# GLCD.net
KiCad netlist of a schematic drawn in Altium Designer
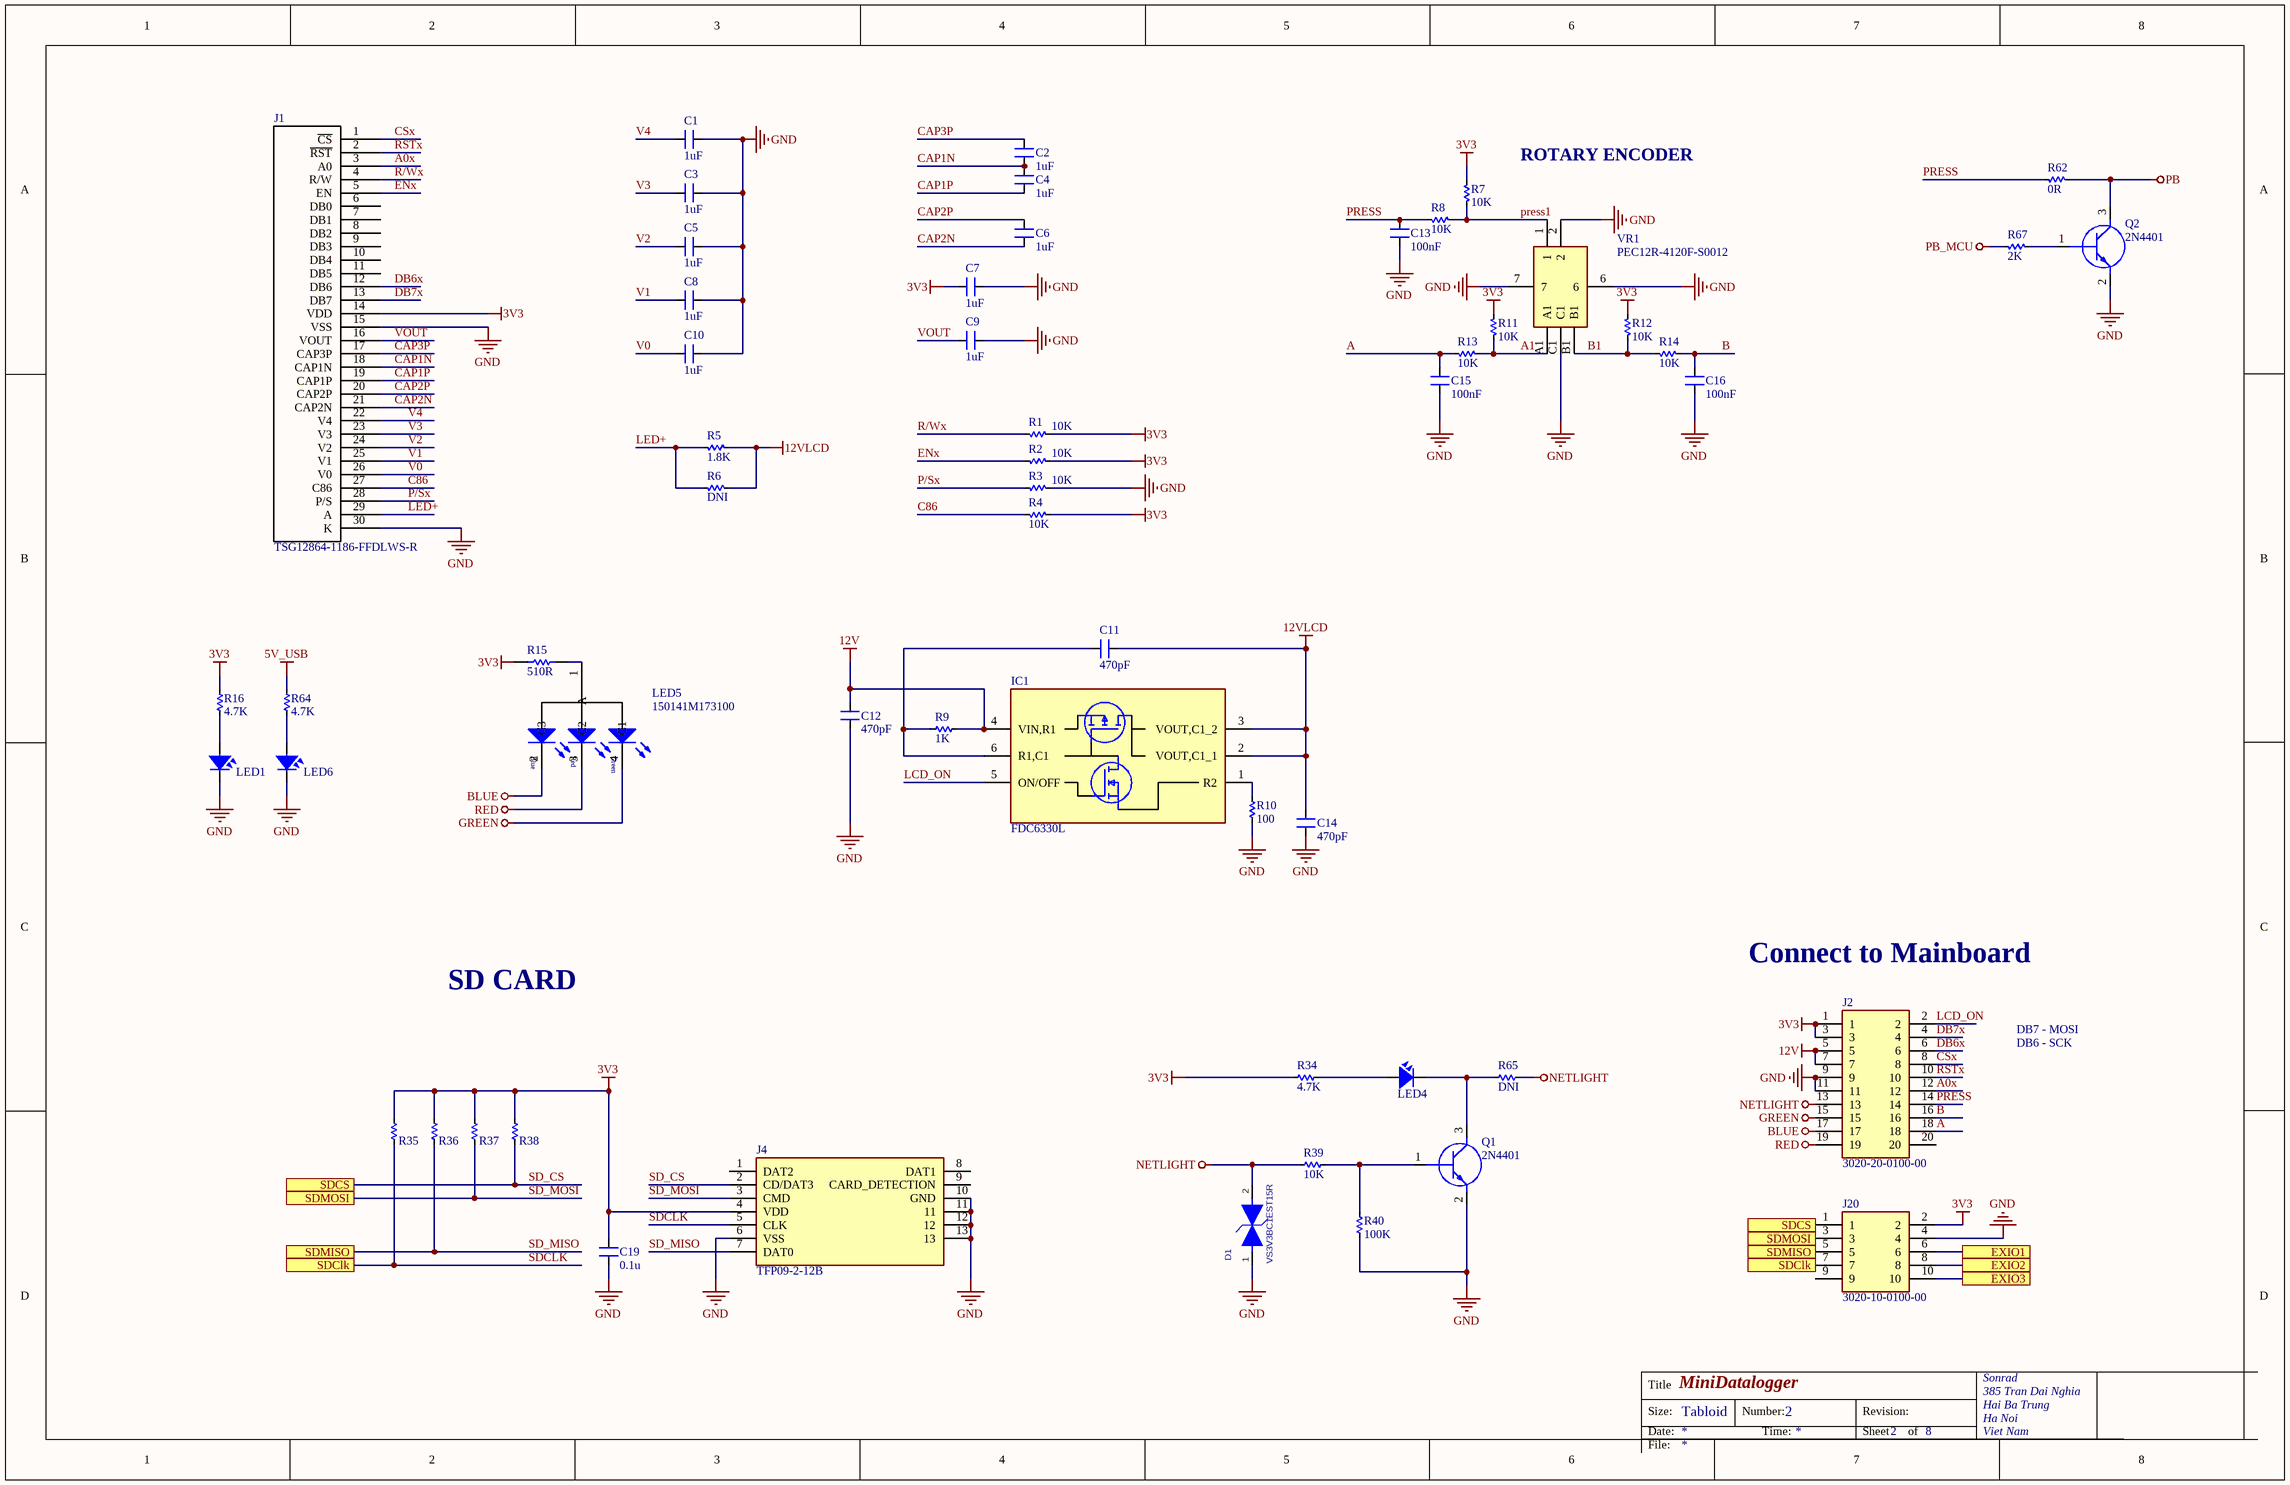
[diagram p0: GLCD.SchDoc]

(export (version "E")
  (design (tool "Eeschema 10.0.6"))
  (components
    (comp (ref "C1")
      (value "1uF")
      (footprint "SM-0805")
      (description "Cap SMD")
      (libsource (lib "hphonglib") (part "CM"))
    )
    (comp (ref "C2")
      (value "1uF")
      (footprint "SM-0805")
      (description "Cap SMD")
      (libsource (lib "hphonglib") (part "CM"))
    )
    (comp (ref "C3")
      (value "1uF")
      (footprint "SM-0805")
      (description "Cap SMD")
      (libsource (lib "hphonglib") (part "CM"))
    )
    (comp (ref "C4")
      (value "1uF")
      (footprint "SM-0805")
      (description "Cap SMD")
      (libsource (lib "hphonglib") (part "CM"))
    )
    (comp (ref "C5")
      (value "1uF")
      (footprint "SM-0805")
      (description "Cap SMD")
      (libsource (lib "hphonglib") (part "CM"))
    )
    (comp (ref "C6")
      (value "1uF")
      (footprint "SM-0805")
      (description "Cap SMD")
      (libsource (lib "hphonglib") (part "CM"))
    )
    (comp (ref "C7")
      (value "1uF")
      (footprint "SM-0805")
      (description "Cap SMD")
      (libsource (lib "hphonglib") (part "CM"))
    )
    (comp (ref "C8")
      (value "1uF")
      (footprint "SM-0805")
      (description "Cap SMD")
      (libsource (lib "hphonglib") (part "CM"))
    )
    (comp (ref "C9")
      (value "1uF")
      (footprint "SM-0805")
      (description "Cap SMD")
      (libsource (lib "hphonglib") (part "CM"))
    )
    (comp (ref "C10")
      (value "1uF")
      (footprint "SM-0805")
      (description "Cap SMD")
      (libsource (lib "hphonglib") (part "CM"))
    )
    (comp (ref "C11")
      (value "470pF")
      (footprint "SM-0805")
      (description "Cap SMD")
      (libsource (lib "hphonglib") (part "CM"))
    )
    (comp (ref "C12")
      (value "470pF")
      (footprint "SM-0805")
      (description "Cap SMD")
      (libsource (lib "hphonglib") (part "CM"))
    )
    (comp (ref "C13")
      (value "100nF")
      (footprint "SM-0805")
      (description "Cap SMD")
      (libsource (lib "hphonglib") (part "CM"))
    )
    (comp (ref "C14")
      (value "470pF")
      (footprint "SM-0805")
      (description "Cap SMD")
      (libsource (lib "hphonglib") (part "CM"))
    )
    (comp (ref "C15")
      (value "100nF")
      (footprint "SM-0805")
      (description "Cap SMD")
      (libsource (lib "hphonglib") (part "CM"))
    )
    (comp (ref "C16")
      (value "100nF")
      (footprint "SM-0805")
      (description "Cap SMD")
      (libsource (lib "hphonglib") (part "CM"))
    )
    (comp (ref "C19")
      (value "0.1u")
      (footprint "SM-0805")
      (description "Cap SMD")
      (libsource (lib "hphonglib") (part "CM"))
    )
    (comp (ref "D1")
      (value "VS3V3BC1EST15R")
      (footprint "0603 RESISTOR")
      (fields
        (field (name "MFR") "WILL")
        (field (name "MPN") "ESD5431N-2/TR")
        (field (name "Comment") "TVS_BI_ESD5431N-2/TR_DFN1006-2L")
      )
      (libsource (lib "*") (part "TVS_BI_ESD5431N-2/TR_DFN1006-2L"))
    )
    (comp (ref "IC1")
      (value "FDC6330L")
      (footprint "SamacSys:SOT95P280X110-6N")
      (description "Integrated Circuit")
      (fields (field (name "MOUSER PART NUMBER") "512-FDC6330L"))
      (libsource (lib "SamacSys") (part "FDC6330L"))
    )
    (comp (ref "J1")
      (value "TSG12864-1186-FFDLWS-R")
      (footprint "TGS2864-1186-FFDLWS-R")
      (libsource (lib "PhanBach") (part "TSG12864-1186-FFDLWS-R"))
    )
    (comp (ref "J2")
      (value "3020-20-0100-00")
      (footprint "SamacSys:SHDR20W65P254_2X10_3302X900X900P")
      (description "Connector")
      (libsource (lib "*") (part "3020-20-0100-00"))
    )
    (comp (ref "J4")
      (value "TFP09-2-12B")
      (footprint "SamacSys:TFP09212B")
      (description "Connector")
      (libsource (lib "SamacSys") (part "TFP09-2-12B"))
    )
    (comp (ref "J20")
      (value "3020-10-0100-00")
      (footprint "SamacSys:SHDR10W65P254_2X5_2032X880X920P")
      (description "Connector")
      (libsource (lib "*") (part "3020-10-0100-00"))
    )
    (comp (ref "LED1") (value "LED") (footprint "LED 3512") (libsource (lib "LIBRARY1") (part "LED SMD")))
    (comp (ref "LED4") (value "LED") (footprint "LED 3512") (libsource (lib "LIBRARY1") (part "LED SMD")))
    (comp (ref "LED5")
      (value "150141M173100")
      (footprint "LED RGB 3528")
      (description "SMD Full-Color Top LED, WL-SFTW, Red & Green & Blue")
      (fields
        (field (name "MANUFACTURER") "Würth Elektronik eiSos GmbH")
        (field (name "CREATED BY") "Christin Otto")
      )
      (libsource (lib "LIBRARY1") (part "LED RGB SMD"))
    )
    (comp (ref "LED6") (value "LED") (footprint "LED 3512") (libsource (lib "LIBRARY1") (part "LED SMD")))
    (comp (ref "Q1")
      (value "2N4401")
      (footprint "SamacSys:SOT96P237X111-3N")
      (description "Transistor BJT NPN")
      (fields
        (field (name "MANUFACTURER_PART_NUMBER") "SBC848BLT1G")
        (field (name "MOUSER PART NUMBER") "863-SBC848BLT1G")
      )
      (libsource (lib "*") (part "SBC848BLT1G"))
    )
    (comp (ref "Q2")
      (value "2N4401")
      (footprint "SamacSys:SOT96P237X111-3N")
      (description "Transistor BJT NPN")
      (fields
        (field (name "MANUFACTURER_PART_NUMBER") "SBC848BLT1G")
        (field (name "MOUSER PART NUMBER") "863-SBC848BLT1G")
      )
      (libsource (lib "*") (part "SBC848BLT1G"))
    )
    (comp (ref "R1")
      (value "10K")
      (footprint "RES-SMD-0805")
      (description "Resistor")
      (fields
        (field (name "MANUFACTURER") "Generic Components")
        (field (name "PUBLISHER") "Altium Hobart Technology Centre")
      )
      (libsource (lib "LIBRARY1") (part "Res-SMD"))
    )
    (comp (ref "R2")
      (value "10K")
      (footprint "RES-SMD-0805")
      (description "Resistor")
      (fields
        (field (name "MANUFACTURER") "Generic Components")
        (field (name "PUBLISHER") "Altium Hobart Technology Centre")
      )
      (libsource (lib "LIBRARY1") (part "Res-SMD"))
    )
    (comp (ref "R3")
      (value "10K")
      (footprint "RES-SMD-0805")
      (description "Resistor")
      (fields
        (field (name "MANUFACTURER") "Generic Components")
        (field (name "PUBLISHER") "Altium Hobart Technology Centre")
      )
      (libsource (lib "LIBRARY1") (part "Res-SMD"))
    )
    (comp (ref "R4")
      (value "10K")
      (footprint "RES-SMD-0805")
      (description "Resistor")
      (fields
        (field (name "MANUFACTURER") "Generic Components")
        (field (name "PUBLISHER") "Altium Hobart Technology Centre")
      )
      (libsource (lib "LIBRARY1") (part "Res-SMD"))
    )
    (comp (ref "R5")
      (value "1.8K")
      (footprint "RES-SMD-0805")
      (description "Resistor")
      (fields
        (field (name "MANUFACTURER") "Generic Components")
        (field (name "PUBLISHER") "Altium Hobart Technology Centre")
      )
      (libsource (lib "LIBRARY1") (part "Res-SMD"))
    )
    (comp (ref "R6")
      (value "DNI")
      (footprint "RES-SMD-0805")
      (description "Resistor")
      (fields
        (field (name "MANUFACTURER") "Generic Components")
        (field (name "PUBLISHER") "Altium Hobart Technology Centre")
      )
      (libsource (lib "LIBRARY1") (part "Res-SMD"))
    )
    (comp (ref "R7")
      (value "10K")
      (footprint "RES-SMD-0805")
      (description "Resistor")
      (fields
        (field (name "MANUFACTURER") "Generic Components")
        (field (name "PUBLISHER") "Altium Hobart Technology Centre")
      )
      (libsource (lib "LIBRARY1") (part "Res-SMD"))
    )
    (comp (ref "R8")
      (value "10K")
      (footprint "RES-SMD-0805")
      (description "Resistor")
      (fields
        (field (name "MANUFACTURER") "Generic Components")
        (field (name "PUBLISHER") "Altium Hobart Technology Centre")
      )
      (libsource (lib "LIBRARY1") (part "Res-SMD"))
    )
    (comp (ref "R9")
      (value "1K")
      (footprint "RES-SMD-0805")
      (description "Resistor")
      (fields
        (field (name "MANUFACTURER") "Generic Components")
        (field (name "PUBLISHER") "Altium Hobart Technology Centre")
      )
      (libsource (lib "LIBRARY1") (part "Res-SMD"))
    )
    (comp (ref "R10")
      (value "100")
      (footprint "RES-SMD-0805")
      (description "Resistor")
      (fields
        (field (name "MANUFACTURER") "Generic Components")
        (field (name "PUBLISHER") "Altium Hobart Technology Centre")
      )
      (libsource (lib "LIBRARY1") (part "Res-SMD"))
    )
    (comp (ref "R11")
      (value "10K")
      (footprint "RES-SMD-0805")
      (description "Resistor")
      (fields
        (field (name "MANUFACTURER") "Generic Components")
        (field (name "PUBLISHER") "Altium Hobart Technology Centre")
      )
      (libsource (lib "LIBRARY1") (part "Res-SMD"))
    )
    (comp (ref "R12")
      (value "10K")
      (footprint "RES-SMD-0805")
      (description "Resistor")
      (fields
        (field (name "MANUFACTURER") "Generic Components")
        (field (name "PUBLISHER") "Altium Hobart Technology Centre")
      )
      (libsource (lib "LIBRARY1") (part "Res-SMD"))
    )
    (comp (ref "R13")
      (value "10K")
      (footprint "RES-SMD-0805")
      (description "Resistor")
      (fields
        (field (name "MANUFACTURER") "Generic Components")
        (field (name "PUBLISHER") "Altium Hobart Technology Centre")
      )
      (libsource (lib "LIBRARY1") (part "Res-SMD"))
    )
    (comp (ref "R14")
      (value "10K")
      (footprint "RES-SMD-0805")
      (description "Resistor")
      (fields
        (field (name "MANUFACTURER") "Generic Components")
        (field (name "PUBLISHER") "Altium Hobart Technology Centre")
      )
      (libsource (lib "LIBRARY1") (part "Res-SMD"))
    )
    (comp (ref "R15")
      (value "510R")
      (footprint "R2012-0805")
      (description "Resistor")
      (libsource (lib "MCD_TOOLS") (part "Res_0_5%_0402"))
    )
    (comp (ref "R16")
      (value "4.7K")
      (footprint "RES-SMD-0805")
      (description "Resistor")
      (fields
        (field (name "MANUFACTURER") "Generic Components")
        (field (name "PUBLISHER") "Altium Hobart Technology Centre")
      )
      (libsource (lib "LIBRARY1") (part "Res-SMD"))
    )
    (comp (ref "R34")
      (value "4.7K")
      (footprint "RES-SMD-0805")
      (description "Resistor")
      (fields
        (field (name "MANUFACTURER") "Generic Components")
        (field (name "PUBLISHER") "Altium Hobart Technology Centre")
      )
      (libsource (lib "LIBRARY1") (part "Res-SMD"))
    )
    (comp (ref "R35")
      (value "100R")
      (footprint "RES-SMD-0805")
      (description "Resistor")
      (fields
        (field (name "MANUFACTURER") "Generic Components")
        (field (name "PUBLISHER") "Altium Hobart Technology Centre")
      )
      (libsource (lib "LIBRARY1") (part "Res-SMD"))
    )
    (comp (ref "R36")
      (value "100R")
      (footprint "RES-SMD-0805")
      (description "Resistor")
      (fields
        (field (name "MANUFACTURER") "Generic Components")
        (field (name "PUBLISHER") "Altium Hobart Technology Centre")
      )
      (libsource (lib "LIBRARY1") (part "Res-SMD"))
    )
    (comp (ref "R37")
      (value "100R")
      (footprint "RES-SMD-0805")
      (description "Resistor")
      (fields
        (field (name "MANUFACTURER") "Generic Components")
        (field (name "PUBLISHER") "Altium Hobart Technology Centre")
      )
      (libsource (lib "LIBRARY1") (part "Res-SMD"))
    )
    (comp (ref "R38")
      (value "100R")
      (footprint "RES-SMD-0805")
      (description "Resistor")
      (fields
        (field (name "MANUFACTURER") "Generic Components")
        (field (name "PUBLISHER") "Altium Hobart Technology Centre")
      )
      (libsource (lib "LIBRARY1") (part "Res-SMD"))
    )
    (comp (ref "R39")
      (value "10K")
      (footprint "RES-SMD-0805")
      (description "Resistor")
      (fields
        (field (name "MANUFACTURER") "Generic Components")
        (field (name "PUBLISHER") "Altium Hobart Technology Centre")
      )
      (libsource (lib "LIBRARY1") (part "Res-SMD"))
    )
    (comp (ref "R40")
      (value "100K")
      (footprint "RES-SMD-0805")
      (description "Resistor")
      (fields
        (field (name "MANUFACTURER") "Generic Components")
        (field (name "PUBLISHER") "Altium Hobart Technology Centre")
      )
      (libsource (lib "LIBRARY1") (part "Res-SMD"))
    )
    (comp (ref "R62")
      (value "0R")
      (footprint "RES-SMD-0805")
      (description "Resistor")
      (fields
        (field (name "MANUFACTURER") "Generic Components")
        (field (name "PUBLISHER") "Altium Hobart Technology Centre")
      )
      (libsource (lib "LIBRARY1") (part "Res-SMD"))
    )
    (comp (ref "R64")
      (value "4.7K")
      (footprint "RES-SMD-0805")
      (description "Resistor")
      (fields
        (field (name "MANUFACTURER") "Generic Components")
        (field (name "PUBLISHER") "Altium Hobart Technology Centre")
      )
      (libsource (lib "LIBRARY1") (part "Res-SMD"))
    )
    (comp (ref "R65")
      (value "DNI")
      (footprint "RES-SMD-0805")
      (description "Resistor")
      (fields
        (field (name "MANUFACTURER") "Generic Components")
        (field (name "PUBLISHER") "Altium Hobart Technology Centre")
      )
      (libsource (lib "LIBRARY1") (part "Res-SMD"))
    )
    (comp (ref "R67")
      (value "2K")
      (footprint "RES-SMD-0805")
      (description "Resistor")
      (fields
        (field (name "MANUFACTURER") "Generic Components")
        (field (name "PUBLISHER") "Altium Hobart Technology Centre")
      )
      (libsource (lib "LIBRARY1") (part "Res-SMD"))
    )
    (comp (ref "VR1")
      (value "PEC12R-4120F-S0012")
      (footprint "EC11-SMD-12.5mm")
      (description "Variable Resistor")
      (fields (field (name "MOUSER PART NUMBER") "652-PEC12R-4120F-S12"))
      (libsource (lib "*") (part "PEC12R-4120F-S0012"))
    )
  )
  (nets
    (net (code "1") (name "/A") (class "Default")
      (node (ref "C15") (pin "2") (pinfunction "2_2") (pintype "passive"))
      (node (ref "J2") (pin "18") (pinfunction "18_18") (pintype "passive"))
      (node (ref "R13") (pin "1") (pinfunction "1_1") (pintype "passive"))
    )
    (net (code "2") (name "/A0x") (class "Default")
      (node (ref "J1") (pin "3") (pinfunction "A0_3") (pintype "passive"))
      (node (ref "J2") (pin "12") (pinfunction "12_12") (pintype "passive"))
    )
    (net (code "3") (name "/A1") (class "Default")
      (node (ref "R11") (pin "1") (pinfunction "1_1") (pintype "passive"))
      (node (ref "R13") (pin "2") (pinfunction "2_2") (pintype "passive"))
      (node (ref "VR1") (pin "A1") (pinfunction "A1_A1") (pintype "passive"))
    )
    (net (code "4") (name "/B") (class "Default")
      (node (ref "C16") (pin "2") (pinfunction "2_2") (pintype "passive"))
      (node (ref "J2") (pin "16") (pinfunction "16_16") (pintype "passive"))
      (node (ref "R14") (pin "2") (pinfunction "2_2") (pintype "passive"))
    )
    (net (code "5") (name "/B1") (class "Default")
      (node (ref "R12") (pin "1") (pinfunction "1_1") (pintype "passive"))
      (node (ref "R14") (pin "1") (pinfunction "1_1") (pintype "passive"))
      (node (ref "VR1") (pin "B1") (pinfunction "B1_B1") (pintype "passive"))
    )
    (net (code "6") (name "/C86") (class "Default")
      (node (ref "J1") (pin "27") (pinfunction "C86_27") (pintype "passive"))
      (node (ref "R4") (pin "1") (pinfunction "1_1") (pintype "passive"))
    )
    (net (code "7") (name "/CAP1N") (class "Default")
      (node (ref "C2") (pin "2") (pinfunction "2_2") (pintype "passive"))
      (node (ref "C4") (pin "1") (pinfunction "1_1") (pintype "passive"))
      (node (ref "J1") (pin "18") (pinfunction "CAP1N_18") (pintype "passive"))
    )
    (net (code "8") (name "/CAP1P") (class "Default")
      (node (ref "C4") (pin "2") (pinfunction "2_2") (pintype "passive"))
      (node (ref "J1") (pin "19") (pinfunction "CAP1P_19") (pintype "passive"))
    )
    (net (code "9") (name "/CAP2N") (class "Default")
      (node (ref "C6") (pin "2") (pinfunction "2_2") (pintype "passive"))
      (node (ref "J1") (pin "21") (pinfunction "CAP2N_21") (pintype "passive"))
    )
    (net (code "10") (name "/CAP2P") (class "Default")
      (node (ref "C6") (pin "1") (pinfunction "1_1") (pintype "passive"))
      (node (ref "J1") (pin "20") (pinfunction "CAP2P_20") (pintype "passive"))
    )
    (net (code "11") (name "/CAP3P") (class "Default")
      (node (ref "C2") (pin "1") (pinfunction "1_1") (pintype "passive"))
      (node (ref "J1") (pin "17") (pinfunction "CAP3P_17") (pintype "passive"))
    )
    (net (code "12") (name "/CSx") (class "Default")
      (node (ref "J1") (pin "1") (pinfunction "~{CS}_1") (pintype "passive"))
      (node (ref "J2") (pin "8") (pinfunction "8_8") (pintype "passive"))
    )
    (net (code "13") (name "/DB6x") (class "Default")
      (node (ref "J1") (pin "12") (pinfunction "DB6_12") (pintype "passive"))
      (node (ref "J2") (pin "6") (pinfunction "6_6") (pintype "passive"))
    )
    (net (code "14") (name "/DB7x") (class "Default")
      (node (ref "J1") (pin "13") (pinfunction "DB7_13") (pintype "passive"))
      (node (ref "J2") (pin "4") (pinfunction "4_4") (pintype "passive"))
    )
    (net (code "15") (name "/ENx") (class "Default")
      (node (ref "J1") (pin "5") (pinfunction "EN_5") (pintype "passive"))
      (node (ref "R2") (pin "1") (pinfunction "1_1") (pintype "passive"))
    )
    (net (code "16") (name "/EXIO1") (class "Default")
      (node (ref "J20") (pin "6") (pinfunction "6_6") (pintype "passive"))
    )
    (net (code "17") (name "/EXIO2") (class "Default")
      (node (ref "J20") (pin "8") (pinfunction "8_8") (pintype "passive"))
    )
    (net (code "18") (name "/EXIO3") (class "Default")
      (node (ref "J20") (pin "10") (pinfunction "10_10") (pintype "passive"))
    )
    (net (code "19") (name "/LCD_ON") (class "Default")
      (node (ref "IC1") (pin "5") (pinfunction "ON/OFF_5") (pintype "passive"))
      (node (ref "J2") (pin "2") (pinfunction "2_2") (pintype "passive"))
    )
    (net (code "20") (name "/LED+") (class "Default")
      (node (ref "J1") (pin "29") (pinfunction "A_29") (pintype "passive"))
      (node (ref "R5") (pin "1") (pinfunction "1_1") (pintype "passive"))
      (node (ref "R6") (pin "1") (pinfunction "1_1") (pintype "passive"))
    )
    (net (code "21") (name "/PRESS") (class "Default")
      (node (ref "C13") (pin "2") (pinfunction "2_2") (pintype "passive"))
      (node (ref "J2") (pin "14") (pinfunction "14_14") (pintype "passive"))
      (node (ref "R62") (pin "2") (pinfunction "2_2") (pintype "passive"))
      (node (ref "R8") (pin "2") (pinfunction "2_2") (pintype "passive"))
    )
    (net (code "22") (name "/P{slash}Sx") (class "Default")
      (node (ref "J1") (pin "28") (pinfunction "P/S_28") (pintype "passive"))
      (node (ref "R3") (pin "1") (pinfunction "1_1") (pintype "passive"))
    )
    (net (code "23") (name "/RSTx") (class "Default")
      (node (ref "J1") (pin "2") (pinfunction "~{RST}_2") (pintype "passive"))
      (node (ref "J2") (pin "10") (pinfunction "10_10") (pintype "passive"))
    )
    (net (code "24") (name "/R{slash}Wx") (class "Default")
      (node (ref "J1") (pin "4") (pinfunction "R/W_4") (pintype "passive"))
      (node (ref "R1") (pin "1") (pinfunction "1_1") (pintype "passive"))
    )
    (net (code "25") (name "/SDCLK") (class "Default")
      (node (ref "J20") (pin "7") (pinfunction "7_7") (pintype "passive"))
      (node (ref "J4") (pin "5") (pinfunction "CLK_5") (pintype "passive"))
      (node (ref "R35") (pin "1") (pinfunction "1_1") (pintype "passive"))
    )
    (net (code "26") (name "/SD_CS") (class "Default")
      (node (ref "J20") (pin "1") (pinfunction "1_1") (pintype "passive"))
      (node (ref "J4") (pin "2") (pinfunction "CD/DAT3_2") (pintype "passive"))
      (node (ref "R38") (pin "1") (pinfunction "1_1") (pintype "passive"))
    )
    (net (code "27") (name "/SD_MISO") (class "Default")
      (node (ref "J20") (pin "5") (pinfunction "5_5") (pintype "passive"))
      (node (ref "J4") (pin "7") (pinfunction "DAT0_7") (pintype "passive"))
      (node (ref "R36") (pin "1") (pinfunction "1_1") (pintype "passive"))
    )
    (net (code "28") (name "/SD_MOSI") (class "Default")
      (node (ref "J20") (pin "3") (pinfunction "3_3") (pintype "passive"))
      (node (ref "J4") (pin "3") (pinfunction "CMD_3") (pintype "passive"))
      (node (ref "R37") (pin "1") (pinfunction "1_1") (pintype "passive"))
    )
    (net (code "29") (name "/V0") (class "Default")
      (node (ref "C10") (pin "2") (pinfunction "2_2") (pintype "passive"))
      (node (ref "J1") (pin "26") (pinfunction "V0_26") (pintype "passive"))
    )
    (net (code "30") (name "/V1") (class "Default")
      (node (ref "C8") (pin "2") (pinfunction "2_2") (pintype "passive"))
      (node (ref "J1") (pin "25") (pinfunction "V1_25") (pintype "passive"))
    )
    (net (code "31") (name "/V2") (class "Default")
      (node (ref "C5") (pin "2") (pinfunction "2_2") (pintype "passive"))
      (node (ref "J1") (pin "24") (pinfunction "V2_24") (pintype "passive"))
    )
    (net (code "32") (name "/V3") (class "Default")
      (node (ref "C3") (pin "2") (pinfunction "2_2") (pintype "passive"))
      (node (ref "J1") (pin "23") (pinfunction "V3_23") (pintype "passive"))
    )
    (net (code "33") (name "/V4") (class "Default")
      (node (ref "C1") (pin "2") (pinfunction "2_2") (pintype "passive"))
      (node (ref "J1") (pin "22") (pinfunction "V4_22") (pintype "passive"))
    )
    (net (code "34") (name "/VOUT") (class "Default")
      (node (ref "C9") (pin "1") (pinfunction "1_1") (pintype "passive"))
      (node (ref "J1") (pin "16") (pinfunction "VOUT_16") (pintype "passive"))
    )
    (net (code "35") (name "/press1") (class "Default")
      (node (ref "R7") (pin "1") (pinfunction "1_1") (pintype "passive"))
      (node (ref "R8") (pin "1") (pinfunction "1_1") (pintype "passive"))
      (node (ref "VR1") (pin "1") (pinfunction "1_1") (pintype "passive"))
    )
    (net (code "36") (name "3V3") (class "Default")
      (node (ref "C19") (pin "2") (pinfunction "2_2") (pintype "passive"))
      (node (ref "C7") (pin "1") (pinfunction "1_1") (pintype "passive"))
      (node (ref "J1") (pin "14") (pinfunction "VDD_14") (pintype "passive"))
      (node (ref "J2") (pin "1") (pinfunction "1_1") (pintype "passive"))
      (node (ref "J2") (pin "3") (pinfunction "3_3") (pintype "passive"))
      (node (ref "J20") (pin "2") (pinfunction "2_2") (pintype "passive"))
      (node (ref "J4") (pin "4") (pinfunction "VDD_4") (pintype "passive"))
      (node (ref "R1") (pin "2") (pinfunction "2_2") (pintype "passive"))
      (node (ref "R11") (pin "2") (pinfunction "2_2") (pintype "passive"))
      (node (ref "R12") (pin "2") (pinfunction "2_2") (pintype "passive"))
      (node (ref "R15") (pin "2") (pinfunction "2_2") (pintype "passive"))
      (node (ref "R16") (pin "1") (pinfunction "1_1") (pintype "passive"))
      (node (ref "R2") (pin "2") (pinfunction "2_2") (pintype "passive"))
      (node (ref "R34") (pin "2") (pinfunction "2_2") (pintype "passive"))
      (node (ref "R35") (pin "2") (pinfunction "2_2") (pintype "passive"))
      (node (ref "R36") (pin "2") (pinfunction "2_2") (pintype "passive"))
      (node (ref "R37") (pin "2") (pinfunction "2_2") (pintype "passive"))
      (node (ref "R38") (pin "2") (pinfunction "2_2") (pintype "passive"))
      (node (ref "R4") (pin "2") (pinfunction "2_2") (pintype "passive"))
      (node (ref "R7") (pin "2") (pinfunction "2_2") (pintype "passive"))
    )
    (net (code "37") (name "5V_USB") (class "Default")
      (node (ref "R64") (pin "1") (pinfunction "1_1") (pintype "passive"))
    )
    (net (code "38") (name "12V") (class "Default")
      (node (ref "C12") (pin "2") (pinfunction "2_2") (pintype "passive"))
      (node (ref "IC1") (pin "4") (pinfunction "VIN,R1_4") (pintype "passive"))
      (node (ref "J2") (pin "5") (pinfunction "5_5") (pintype "passive"))
      (node (ref "J2") (pin "7") (pinfunction "7_7") (pintype "passive"))
      (node (ref "R9") (pin "1") (pinfunction "1_1") (pintype "passive"))
    )
    (net (code "39") (name "12VLCD") (class "Default")
      (node (ref "C11") (pin "2") (pinfunction "2_2") (pintype "passive"))
      (node (ref "C14") (pin "1") (pinfunction "1_1") (pintype "passive"))
      (node (ref "IC1") (pin "2") (pinfunction "VOUT,C1_1_2") (pintype "passive"))
      (node (ref "IC1") (pin "3") (pinfunction "VOUT,C1_2_3") (pintype "passive"))
      (node (ref "R5") (pin "2") (pinfunction "2_2") (pintype "passive"))
      (node (ref "R6") (pin "2") (pinfunction "2_2") (pintype "passive"))
    )
    (net (code "40") (name "BLUE") (class "Default")
      (node (ref "J2") (pin "17") (pinfunction "17_17") (pintype "passive"))
      (node (ref "LED5") (pin "2") (pinfunction "C3_2") (pintype "passive"))
    )
    (net (code "41") (name "GND") (class "Default")
      (node (ref "C1") (pin "1") (pinfunction "1_1") (pintype "passive"))
      (node (ref "C10") (pin "1") (pinfunction "1_1") (pintype "passive"))
      (node (ref "C12") (pin "1") (pinfunction "1_1") (pintype "passive"))
      (node (ref "C13") (pin "1") (pinfunction "1_1") (pintype "passive"))
      (node (ref "C14") (pin "2") (pinfunction "2_2") (pintype "passive"))
      (node (ref "C15") (pin "1") (pinfunction "1_1") (pintype "passive"))
      (node (ref "C16") (pin "1") (pinfunction "1_1") (pintype "passive"))
      (node (ref "C19") (pin "1") (pinfunction "1_1") (pintype "passive"))
      (node (ref "C3") (pin "1") (pinfunction "1_1") (pintype "passive"))
      (node (ref "C5") (pin "1") (pinfunction "1_1") (pintype "passive"))
      (node (ref "C7") (pin "2") (pinfunction "2_2") (pintype "passive"))
      (node (ref "C8") (pin "1") (pinfunction "1_1") (pintype "passive"))
      (node (ref "C9") (pin "2") (pinfunction "2_2") (pintype "passive"))
      (node (ref "D1") (pin "1") (pinfunction "1_1") (pintype "passive"))
      (node (ref "J1") (pin "15") (pinfunction "VSS_15") (pintype "passive"))
      (node (ref "J1") (pin "30") (pinfunction "K_30") (pintype "passive"))
      (node (ref "J2") (pin "11") (pinfunction "11_11") (pintype "passive"))
      (node (ref "J2") (pin "9") (pinfunction "9_9") (pintype "passive"))
      (node (ref "J20") (pin "4") (pinfunction "4_4") (pintype "passive"))
      (node (ref "J4") (pin "10") (pinfunction "GND_10") (pintype "passive"))
      (node (ref "J4") (pin "11") (pinfunction "11_11") (pintype "passive"))
      (node (ref "J4") (pin "12") (pinfunction "12_12") (pintype "passive"))
      (node (ref "J4") (pin "13") (pinfunction "13_13") (pintype "passive"))
      (node (ref "J4") (pin "6") (pinfunction "VSS_6") (pintype "passive"))
      (node (ref "LED1") (pin "2") (pinfunction "2_2") (pintype "passive"))
      (node (ref "LED6") (pin "2") (pinfunction "2_2") (pintype "passive"))
      (node (ref "Q1") (pin "2") (pinfunction "E_2") (pintype "passive"))
      (node (ref "Q2") (pin "2") (pinfunction "E_2") (pintype "passive"))
      (node (ref "R10") (pin "1") (pinfunction "1_1") (pintype "passive"))
      (node (ref "R3") (pin "2") (pinfunction "2_2") (pintype "passive"))
      (node (ref "R40") (pin "1") (pinfunction "1_1") (pintype "passive"))
      (node (ref "VR1") (pin "2") (pinfunction "2_2") (pintype "passive"))
      (node (ref "VR1") (pin "6") (pinfunction "6_6") (pintype "passive"))
      (node (ref "VR1") (pin "7") (pinfunction "7_7") (pintype "passive"))
      (node (ref "VR1") (pin "C1") (pinfunction "C1_C1") (pintype "passive"))
    )
    (net (code "42") (name "GREEN") (class "Default")
      (node (ref "J2") (pin "15") (pinfunction "15_15") (pintype "passive"))
      (node (ref "LED5") (pin "4") (pinfunction "C1_4") (pintype "passive"))
    )
    (net (code "43") (name "NETLIGHT") (class "Default")
      (node (ref "D1") (pin "2") (pinfunction "2_2") (pintype "passive"))
      (node (ref "J2") (pin "13") (pinfunction "13_13") (pintype "passive"))
      (node (ref "R39") (pin "2") (pinfunction "2_2") (pintype "passive"))
      (node (ref "R65") (pin "1") (pinfunction "1_1") (pintype "passive"))
    )
    (net (code "44") (name "Net-(IC1-R1,C1)") (class "Default")
      (node (ref "C11") (pin "1") (pinfunction "1_1") (pintype "passive"))
      (node (ref "IC1") (pin "6") (pinfunction "R1,C1_6") (pintype "passive"))
      (node (ref "R9") (pin "2") (pinfunction "2_2") (pintype "passive"))
    )
    (net (code "45") (name "Net-(IC1-R2)") (class "Default")
      (node (ref "IC1") (pin "1") (pinfunction "R2_1") (pintype "passive"))
      (node (ref "R10") (pin "2") (pinfunction "2_2") (pintype "passive"))
    )
    (net (code "46") (name "Net-(LED1-Pad1)") (class "Default")
      (node (ref "LED1") (pin "1") (pinfunction "1_1") (pintype "passive"))
      (node (ref "R16") (pin "2") (pinfunction "2_2") (pintype "passive"))
    )
    (net (code "47") (name "Net-(LED4-Pad1)") (class "Default")
      (node (ref "LED4") (pin "1") (pinfunction "1_1") (pintype "passive"))
      (node (ref "R34") (pin "1") (pinfunction "1_1") (pintype "passive"))
    )
    (net (code "48") (name "Net-(LED5-A)") (class "Default")
      (node (ref "LED5") (pin "1") (pinfunction "A_1") (pintype "passive"))
      (node (ref "R15") (pin "1") (pinfunction "1_1") (pintype "passive"))
    )
    (net (code "49") (name "Net-(LED6-Pad1)") (class "Default")
      (node (ref "LED6") (pin "1") (pinfunction "1_1") (pintype "passive"))
      (node (ref "R64") (pin "2") (pinfunction "2_2") (pintype "passive"))
    )
    (net (code "50") (name "Net-(Q1-B)") (class "Default")
      (node (ref "Q1") (pin "1") (pinfunction "B_1") (pintype "passive"))
      (node (ref "R39") (pin "1") (pinfunction "1_1") (pintype "passive"))
      (node (ref "R40") (pin "2") (pinfunction "2_2") (pintype "passive"))
    )
    (net (code "51") (name "Net-(Q1-C)") (class "Default")
      (node (ref "LED4") (pin "2") (pinfunction "2_2") (pintype "passive"))
      (node (ref "Q1") (pin "3") (pinfunction "C_3") (pintype "passive"))
      (node (ref "R65") (pin "2") (pinfunction "2_2") (pintype "passive"))
    )
    (net (code "52") (name "Net-(Q2-B)") (class "Default")
      (node (ref "Q2") (pin "1") (pinfunction "B_1") (pintype "passive"))
      (node (ref "R67") (pin "1") (pinfunction "1_1") (pintype "passive"))
    )
    (net (code "53") (name "PB") (class "Default")
      (node (ref "Q2") (pin "3") (pinfunction "C_3") (pintype "passive"))
      (node (ref "R62") (pin "1") (pinfunction "1_1") (pintype "passive"))
    )
    (net (code "54") (name "PB_MCU") (class "Default")
      (node (ref "R67") (pin "2") (pinfunction "2_2") (pintype "passive"))
    )
    (net (code "55") (name "RED") (class "Default")
      (node (ref "J2") (pin "19") (pinfunction "19_19") (pintype "passive"))
      (node (ref "LED5") (pin "3") (pinfunction "C2_3") (pintype "passive"))
    )
    (net (code "56") (name "unconnected-(J1-DB0-Pad6)") (class "Default")
      (node (ref "J1") (pin "6") (pinfunction "DB0_6") (pintype "passive"))
    )
    (net (code "57") (name "unconnected-(J1-DB1-Pad7)") (class "Default")
      (node (ref "J1") (pin "7") (pinfunction "DB1_7") (pintype "passive"))
    )
    (net (code "58") (name "unconnected-(J1-DB2-Pad8)") (class "Default")
      (node (ref "J1") (pin "8") (pinfunction "DB2_8") (pintype "passive"))
    )
    (net (code "59") (name "unconnected-(J1-DB3-Pad9)") (class "Default")
      (node (ref "J1") (pin "9") (pinfunction "DB3_9") (pintype "passive"))
    )
    (net (code "60") (name "unconnected-(J1-DB4-Pad10)") (class "Default")
      (node (ref "J1") (pin "10") (pinfunction "DB4_10") (pintype "passive"))
    )
    (net (code "61") (name "unconnected-(J1-DB5-Pad11)") (class "Default")
      (node (ref "J1") (pin "11") (pinfunction "DB5_11") (pintype "passive"))
    )
    (net (code "62") (name "unconnected-(J2-Pad20)") (class "Default")
      (node (ref "J2") (pin "20") (pinfunction "20_20") (pintype "passive"))
    )
    (net (code "63") (name "unconnected-(J4-CARD_DETECTION-Pad9)") (class "Default")
      (node (ref "J4") (pin "9") (pinfunction "CARD_DETECTION_9") (pintype "passive"))
    )
    (net (code "64") (name "unconnected-(J4-DAT1-Pad8)") (class "Default")
      (node (ref "J4") (pin "8") (pinfunction "DAT1_8") (pintype "passive"))
    )
    (net (code "65") (name "unconnected-(J4-DAT2-Pad1)") (class "Default")
      (node (ref "J4") (pin "1") (pinfunction "DAT2_1") (pintype "passive"))
    )
    (net (code "66") (name "unconnected-(J20-Pad9)") (class "Default")
      (node (ref "J20") (pin "9") (pinfunction "9_9") (pintype "passive"))
    )
  )
)
